# M623X.net
KiCad netlist of a schematic drawn in EAGLE
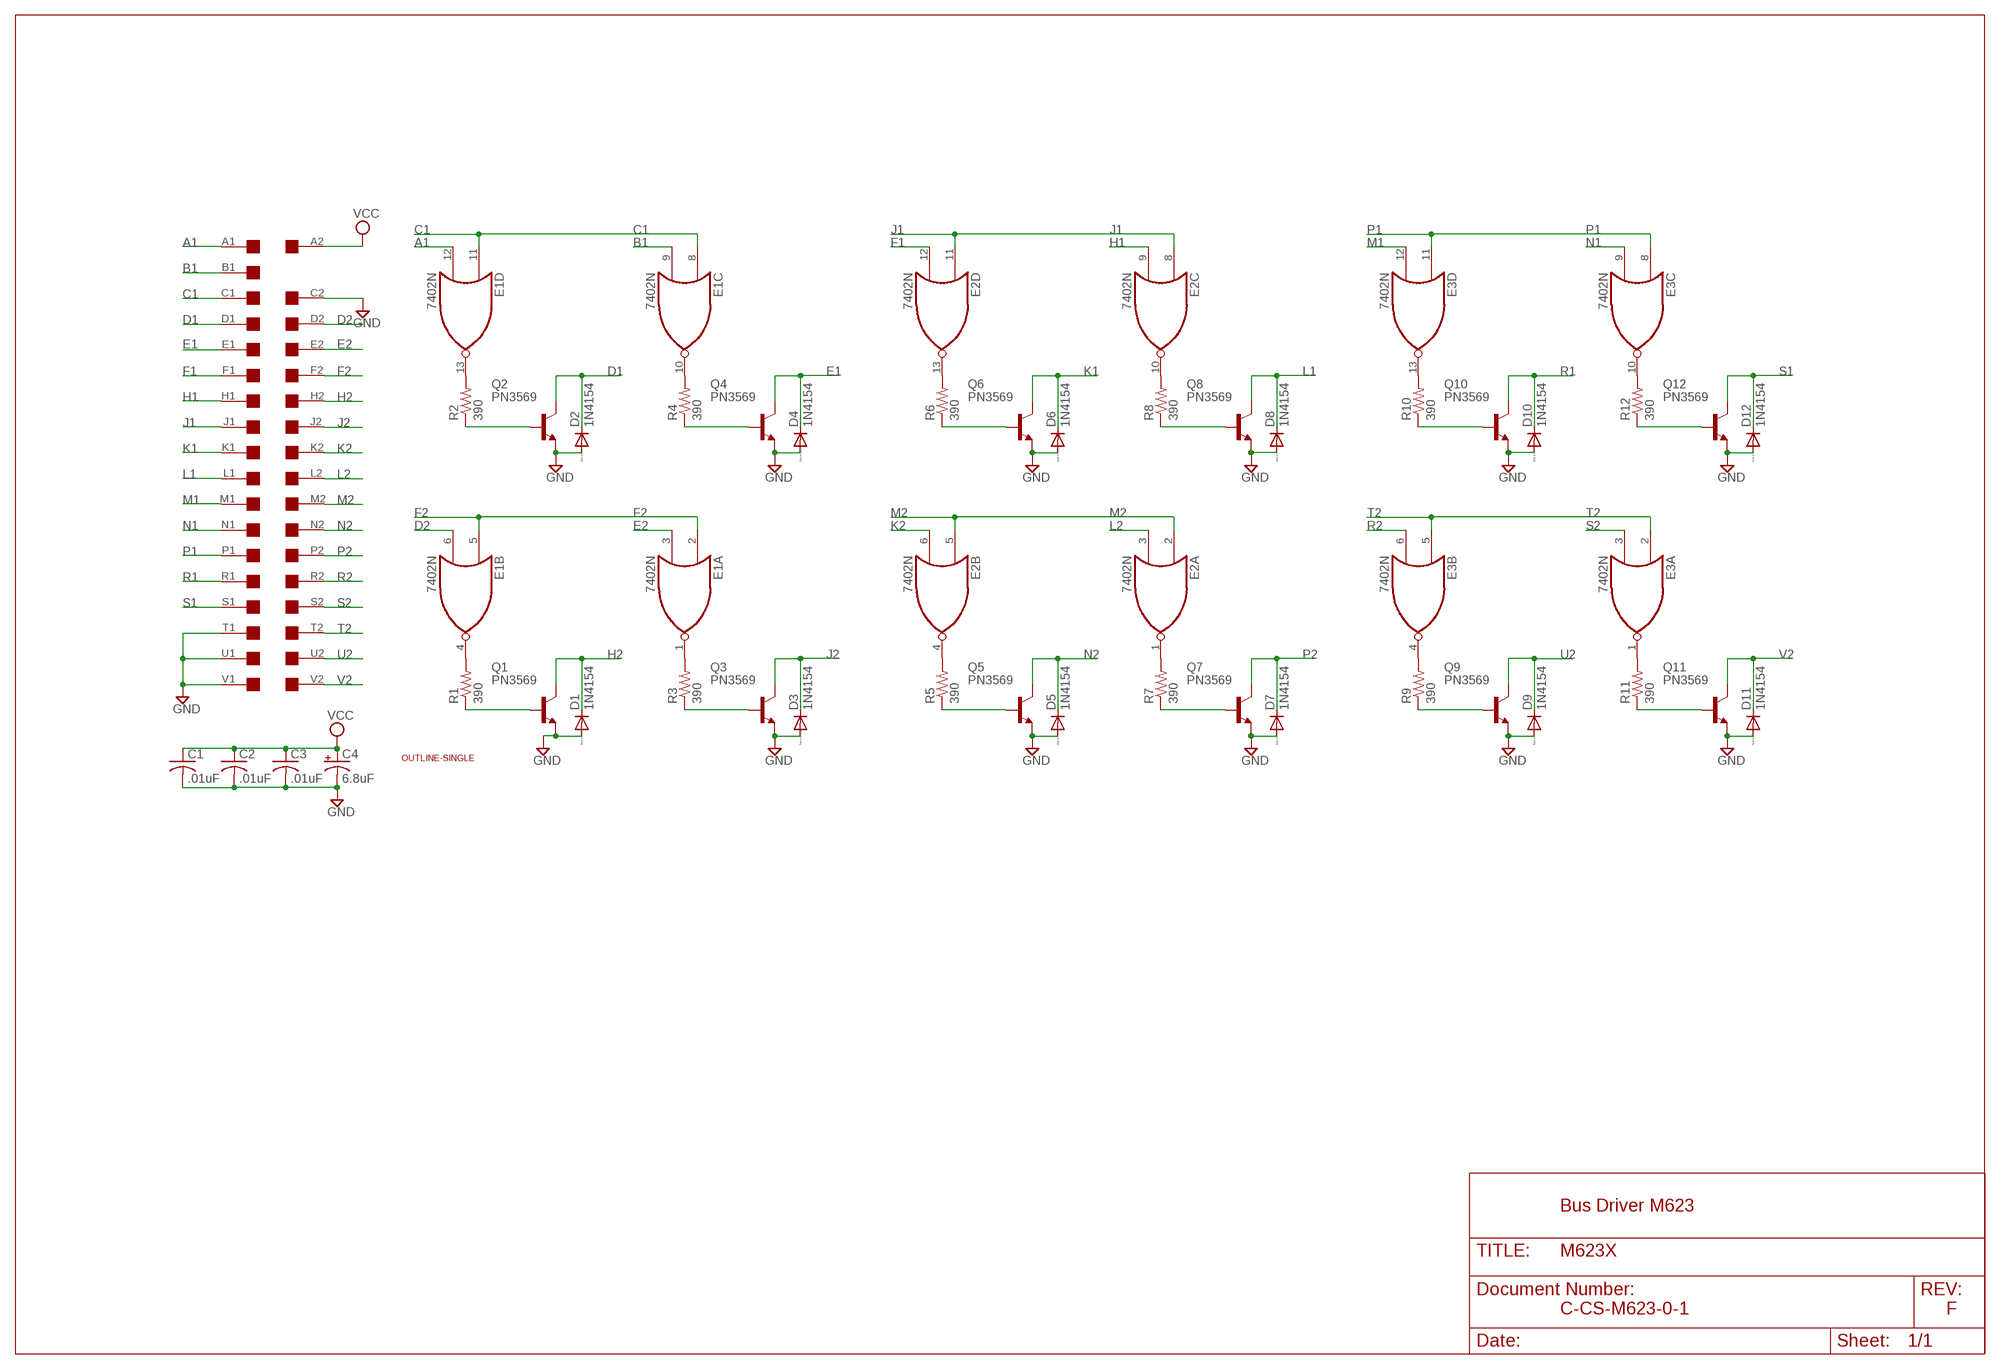
[diagram p0: schematic, sheet 1]

(export (version "E")
  (design (tool "Eeschema 10.0.6"))
  (components
    (comp (ref "C1")
      (value ".01uF")
      (footprint "eagle-import:C050-025X075")
      (libsource (lib "eagle-import") (part "C-US050-025X075"))
    )
    (comp (ref "C2")
      (value ".01uF")
      (footprint "eagle-import:C050-025X075")
      (libsource (lib "eagle-import") (part "C-US050-025X075"))
    )
    (comp (ref "C3")
      (value ".01uF")
      (footprint "eagle-import:C050-025X075")
      (libsource (lib "eagle-import") (part "C-US050-025X075"))
    )
    (comp (ref "C4")
      (value "6.8uF")
      (footprint "eagle-import:E12-8")
      (libsource (lib "eagle-import") (part "CPOL-USE20-8AXIAL"))
    )
    (comp (ref "D1")
      (value "1N4154")
      (footprint "eagle-import:DO35-10")
      (libsource (lib "eagle-import") (part "1N4148DO35-10"))
    )
    (comp (ref "D2")
      (value "1N4154")
      (footprint "eagle-import:DO35-10")
      (libsource (lib "eagle-import") (part "1N4148DO35-10"))
    )
    (comp (ref "D3")
      (value "1N4154")
      (footprint "eagle-import:DO35-10")
      (libsource (lib "eagle-import") (part "1N4148DO35-10"))
    )
    (comp (ref "D4")
      (value "1N4154")
      (footprint "eagle-import:DO35-10")
      (libsource (lib "eagle-import") (part "1N4148DO35-10"))
    )
    (comp (ref "D5")
      (value "1N4154")
      (footprint "eagle-import:DO35-10")
      (libsource (lib "eagle-import") (part "1N4148DO35-10"))
    )
    (comp (ref "D6")
      (value "1N4154")
      (footprint "eagle-import:DO35-10")
      (libsource (lib "eagle-import") (part "1N4148DO35-10"))
    )
    (comp (ref "D7")
      (value "1N4154")
      (footprint "eagle-import:DO35-10")
      (libsource (lib "eagle-import") (part "1N4148DO35-10"))
    )
    (comp (ref "D8")
      (value "1N4154")
      (footprint "eagle-import:DO35-10")
      (libsource (lib "eagle-import") (part "1N4148DO35-10"))
    )
    (comp (ref "D9")
      (value "1N4154")
      (footprint "eagle-import:DO35-10")
      (libsource (lib "eagle-import") (part "1N4148DO35-10"))
    )
    (comp (ref "D10")
      (value "1N4154")
      (footprint "eagle-import:DO35-10")
      (libsource (lib "eagle-import") (part "1N4148DO35-10"))
    )
    (comp (ref "D11")
      (value "1N4154")
      (footprint "eagle-import:DO35-10")
      (libsource (lib "eagle-import") (part "1N4148DO35-10"))
    )
    (comp (ref "D12")
      (value "1N4154")
      (footprint "eagle-import:DO35-10")
      (libsource (lib "eagle-import") (part "1N4148DO35-10"))
    )
    (comp (ref "E1")
      (value "7402N")
      (footprint "eagle-import:DIL14")
      (libsource (lib "eagle-import") (part "7402N"))
    )
    (comp (ref "E2")
      (value "7402N")
      (footprint "eagle-import:DIL14")
      (libsource (lib "eagle-import") (part "7402N"))
    )
    (comp (ref "E3")
      (value "7402N")
      (footprint "eagle-import:DIL14")
      (libsource (lib "eagle-import") (part "7402N"))
    )
    (comp (ref "Q1")
      (value "PN3569")
      (footprint "eagle-import:TO39")
      (libsource (lib "eagle-import") (part "-NPN-TO39-EBC2N1613"))
    )
    (comp (ref "Q2")
      (value "PN3569")
      (footprint "eagle-import:TO39")
      (libsource (lib "eagle-import") (part "-NPN-TO39-EBC2N1613"))
    )
    (comp (ref "Q3")
      (value "PN3569")
      (footprint "eagle-import:TO39")
      (libsource (lib "eagle-import") (part "-NPN-TO39-EBC2N1613"))
    )
    (comp (ref "Q4")
      (value "PN3569")
      (footprint "eagle-import:TO39")
      (libsource (lib "eagle-import") (part "-NPN-TO39-EBC2N1613"))
    )
    (comp (ref "Q5")
      (value "PN3569")
      (footprint "eagle-import:TO39")
      (libsource (lib "eagle-import") (part "-NPN-TO39-EBC2N1613"))
    )
    (comp (ref "Q6")
      (value "PN3569")
      (footprint "eagle-import:TO39")
      (libsource (lib "eagle-import") (part "-NPN-TO39-EBC2N1613"))
    )
    (comp (ref "Q7")
      (value "PN3569")
      (footprint "eagle-import:TO39")
      (libsource (lib "eagle-import") (part "-NPN-TO39-EBC2N1613"))
    )
    (comp (ref "Q8")
      (value "PN3569")
      (footprint "eagle-import:TO39")
      (libsource (lib "eagle-import") (part "-NPN-TO39-EBC2N1613"))
    )
    (comp (ref "Q9")
      (value "PN3569")
      (footprint "eagle-import:TO39")
      (libsource (lib "eagle-import") (part "-NPN-TO39-EBC2N1613"))
    )
    (comp (ref "Q10")
      (value "PN3569")
      (footprint "eagle-import:TO39")
      (libsource (lib "eagle-import") (part "-NPN-TO39-EBC2N1613"))
    )
    (comp (ref "Q11")
      (value "PN3569")
      (footprint "eagle-import:TO39")
      (libsource (lib "eagle-import") (part "-NPN-TO39-EBC2N1613"))
    )
    (comp (ref "Q12")
      (value "PN3569")
      (footprint "eagle-import:TO39")
      (libsource (lib "eagle-import") (part "-NPN-TO39-EBC2N1613"))
    )
    (comp (ref "R1")
      (value "390")
      (footprint "eagle-import:0207_10")
      (libsource (lib "eagle-import") (part "R-US_0207/10"))
    )
    (comp (ref "R2")
      (value "390")
      (footprint "eagle-import:0207_10")
      (libsource (lib "eagle-import") (part "R-US_0207/10"))
    )
    (comp (ref "R3")
      (value "390")
      (footprint "eagle-import:0207_10")
      (libsource (lib "eagle-import") (part "R-US_0207/10"))
    )
    (comp (ref "R4")
      (value "390")
      (footprint "eagle-import:0207_10")
      (libsource (lib "eagle-import") (part "R-US_0207/10"))
    )
    (comp (ref "R5")
      (value "390")
      (footprint "eagle-import:0207_10")
      (libsource (lib "eagle-import") (part "R-US_0207/10"))
    )
    (comp (ref "R6")
      (value "390")
      (footprint "eagle-import:0207_10")
      (libsource (lib "eagle-import") (part "R-US_0207/10"))
    )
    (comp (ref "R7")
      (value "390")
      (footprint "eagle-import:0207_10")
      (libsource (lib "eagle-import") (part "R-US_0207/10"))
    )
    (comp (ref "R8")
      (value "390")
      (footprint "eagle-import:0207_10")
      (libsource (lib "eagle-import") (part "R-US_0207/10"))
    )
    (comp (ref "R9")
      (value "390")
      (footprint "eagle-import:0207_10")
      (libsource (lib "eagle-import") (part "R-US_0207/10"))
    )
    (comp (ref "R10")
      (value "390")
      (footprint "eagle-import:0207_10")
      (libsource (lib "eagle-import") (part "R-US_0207/10"))
    )
    (comp (ref "R11")
      (value "390")
      (footprint "eagle-import:0207_10")
      (libsource (lib "eagle-import") (part "R-US_0207/10"))
    )
    (comp (ref "R12")
      (value "390")
      (footprint "eagle-import:0207_10")
      (libsource (lib "eagle-import") (part "R-US_0207/10"))
    )
    (comp (ref "U$1")
      (value "OUTLINE-SINGLE")
      (footprint "eagle-import:SINGLE")
      (libsource (lib "eagle-import") (part "OUTLINE-SINGLE"))
    )
    (comp (ref "U$4")
      (value "SINGLE")
      (footprint "eagle-import:EDGE-CON2")
      (libsource (lib "eagle-import") (part "SINGLE"))
    )
  )
  (nets
    (net (code "1") (name "/A1") (class "Default")
      (node (ref "E1") (pin "12") (pinfunction "I1_12") (pintype "input"))
      (node (ref "U$4") (pin "A1") (pinfunction "1_A1") (pintype "bidirectional"))
    )
    (net (code "2") (name "/B1") (class "Default")
      (node (ref "E1") (pin "9") (pinfunction "I1_9") (pintype "input"))
      (node (ref "U$4") (pin "B1") (pinfunction "1_B1") (pintype "bidirectional"))
    )
    (net (code "3") (name "/C1") (class "Default")
      (node (ref "E1") (pin "11") (pinfunction "I0_11") (pintype "input"))
      (node (ref "E1") (pin "8") (pinfunction "I0_8") (pintype "input"))
      (node (ref "U$4") (pin "C1") (pinfunction "1_C1") (pintype "bidirectional"))
    )
    (net (code "4") (name "/D1") (class "Default")
      (node (ref "D2") (pin "C") (pinfunction "C_C") (pintype "passive"))
      (node (ref "Q2") (pin "3") (pinfunction "C_3") (pintype "passive"))
      (node (ref "U$4") (pin "D1") (pinfunction "1_D1") (pintype "bidirectional"))
    )
    (net (code "5") (name "/D2") (class "Default")
      (node (ref "E1") (pin "6") (pinfunction "I1_6") (pintype "input"))
      (node (ref "U$4") (pin "D2") (pinfunction "1_D2") (pintype "bidirectional"))
    )
    (net (code "6") (name "/E1") (class "Default")
      (node (ref "D4") (pin "C") (pinfunction "C_C") (pintype "passive"))
      (node (ref "Q4") (pin "3") (pinfunction "C_3") (pintype "passive"))
      (node (ref "U$4") (pin "E1") (pinfunction "1_E1") (pintype "bidirectional"))
    )
    (net (code "7") (name "/E2") (class "Default")
      (node (ref "E1") (pin "3") (pinfunction "I1_3") (pintype "input"))
      (node (ref "U$4") (pin "E2") (pinfunction "1_E2") (pintype "bidirectional"))
    )
    (net (code "8") (name "/F1") (class "Default")
      (node (ref "E2") (pin "12") (pinfunction "I1_12") (pintype "input"))
      (node (ref "U$4") (pin "F1") (pinfunction "1_F1") (pintype "bidirectional"))
    )
    (net (code "9") (name "/F2") (class "Default")
      (node (ref "E1") (pin "2") (pinfunction "I0_2") (pintype "input"))
      (node (ref "E1") (pin "5") (pinfunction "I0_5") (pintype "input"))
      (node (ref "U$4") (pin "F2") (pinfunction "1_F2") (pintype "bidirectional"))
    )
    (net (code "10") (name "/H1") (class "Default")
      (node (ref "E2") (pin "9") (pinfunction "I1_9") (pintype "input"))
      (node (ref "U$4") (pin "H1") (pinfunction "1_H1") (pintype "bidirectional"))
    )
    (net (code "11") (name "/H2") (class "Default")
      (node (ref "D1") (pin "C") (pinfunction "C_C") (pintype "passive"))
      (node (ref "Q1") (pin "3") (pinfunction "C_3") (pintype "passive"))
      (node (ref "U$4") (pin "H2") (pinfunction "1_H2") (pintype "bidirectional"))
    )
    (net (code "12") (name "/J1") (class "Default")
      (node (ref "E2") (pin "11") (pinfunction "I0_11") (pintype "input"))
      (node (ref "E2") (pin "8") (pinfunction "I0_8") (pintype "input"))
      (node (ref "U$4") (pin "J1") (pinfunction "1_J1") (pintype "bidirectional"))
    )
    (net (code "13") (name "/J2") (class "Default")
      (node (ref "D3") (pin "C") (pinfunction "C_C") (pintype "passive"))
      (node (ref "Q3") (pin "3") (pinfunction "C_3") (pintype "passive"))
      (node (ref "U$4") (pin "J2") (pinfunction "1_J2") (pintype "bidirectional"))
    )
    (net (code "14") (name "/K1") (class "Default")
      (node (ref "D6") (pin "C") (pinfunction "C_C") (pintype "passive"))
      (node (ref "Q6") (pin "3") (pinfunction "C_3") (pintype "passive"))
      (node (ref "U$4") (pin "K1") (pinfunction "1_K1") (pintype "bidirectional"))
    )
    (net (code "15") (name "/K2") (class "Default")
      (node (ref "E2") (pin "6") (pinfunction "I1_6") (pintype "input"))
      (node (ref "U$4") (pin "K2") (pinfunction "1_K2") (pintype "bidirectional"))
    )
    (net (code "16") (name "/L1") (class "Default")
      (node (ref "D8") (pin "C") (pinfunction "C_C") (pintype "passive"))
      (node (ref "Q8") (pin "3") (pinfunction "C_3") (pintype "passive"))
      (node (ref "U$4") (pin "L1") (pinfunction "1_L1") (pintype "bidirectional"))
    )
    (net (code "17") (name "/L2") (class "Default")
      (node (ref "E2") (pin "3") (pinfunction "I1_3") (pintype "input"))
      (node (ref "U$4") (pin "L2") (pinfunction "1_L2") (pintype "bidirectional"))
    )
    (net (code "18") (name "/M1") (class "Default")
      (node (ref "E3") (pin "12") (pinfunction "I1_12") (pintype "input"))
      (node (ref "U$4") (pin "M1") (pinfunction "1_M1") (pintype "bidirectional"))
    )
    (net (code "19") (name "/M2") (class "Default")
      (node (ref "E2") (pin "2") (pinfunction "I0_2") (pintype "input"))
      (node (ref "E2") (pin "5") (pinfunction "I0_5") (pintype "input"))
      (node (ref "U$4") (pin "M2") (pinfunction "1_M2") (pintype "bidirectional"))
    )
    (net (code "20") (name "/N1") (class "Default")
      (node (ref "E3") (pin "9") (pinfunction "I1_9") (pintype "input"))
      (node (ref "U$4") (pin "N1") (pinfunction "1_N1") (pintype "bidirectional"))
    )
    (net (code "21") (name "/N2") (class "Default")
      (node (ref "D5") (pin "C") (pinfunction "C_C") (pintype "passive"))
      (node (ref "Q5") (pin "3") (pinfunction "C_3") (pintype "passive"))
      (node (ref "U$4") (pin "N2") (pinfunction "1_N2") (pintype "bidirectional"))
    )
    (net (code "22") (name "/P1") (class "Default")
      (node (ref "E3") (pin "11") (pinfunction "I0_11") (pintype "input"))
      (node (ref "E3") (pin "8") (pinfunction "I0_8") (pintype "input"))
      (node (ref "U$4") (pin "P1") (pinfunction "1_P1") (pintype "bidirectional"))
    )
    (net (code "23") (name "/P2") (class "Default")
      (node (ref "D7") (pin "C") (pinfunction "C_C") (pintype "passive"))
      (node (ref "Q7") (pin "3") (pinfunction "C_3") (pintype "passive"))
      (node (ref "U$4") (pin "P2") (pinfunction "1_P2") (pintype "bidirectional"))
    )
    (net (code "24") (name "/R1") (class "Default")
      (node (ref "D10") (pin "C") (pinfunction "C_C") (pintype "passive"))
      (node (ref "Q10") (pin "3") (pinfunction "C_3") (pintype "passive"))
      (node (ref "U$4") (pin "R1") (pinfunction "1_R1") (pintype "bidirectional"))
    )
    (net (code "25") (name "/R2") (class "Default")
      (node (ref "E3") (pin "6") (pinfunction "I1_6") (pintype "input"))
      (node (ref "U$4") (pin "R2") (pinfunction "1_R2") (pintype "bidirectional"))
    )
    (net (code "26") (name "/S1") (class "Default")
      (node (ref "D12") (pin "C") (pinfunction "C_C") (pintype "passive"))
      (node (ref "Q12") (pin "3") (pinfunction "C_3") (pintype "passive"))
      (node (ref "U$4") (pin "S1") (pinfunction "1_S1") (pintype "bidirectional"))
    )
    (net (code "27") (name "/S2") (class "Default")
      (node (ref "E3") (pin "3") (pinfunction "I1_3") (pintype "input"))
      (node (ref "U$4") (pin "S2") (pinfunction "1_S2") (pintype "bidirectional"))
    )
    (net (code "28") (name "/T2") (class "Default")
      (node (ref "E3") (pin "2") (pinfunction "I0_2") (pintype "input"))
      (node (ref "E3") (pin "5") (pinfunction "I0_5") (pintype "input"))
      (node (ref "U$4") (pin "T2") (pinfunction "1_T2") (pintype "bidirectional"))
    )
    (net (code "29") (name "/U2") (class "Default")
      (node (ref "D9") (pin "C") (pinfunction "C_C") (pintype "passive"))
      (node (ref "Q9") (pin "3") (pinfunction "C_3") (pintype "passive"))
      (node (ref "U$4") (pin "U2") (pinfunction "1_U2") (pintype "bidirectional"))
    )
    (net (code "30") (name "/V2") (class "Default")
      (node (ref "D11") (pin "C") (pinfunction "C_C") (pintype "passive"))
      (node (ref "Q11") (pin "3") (pinfunction "C_3") (pintype "passive"))
      (node (ref "U$4") (pin "V2") (pinfunction "1_V2") (pintype "bidirectional"))
    )
    (net (code "31") (name "GND") (class "Default")
      (node (ref "C1") (pin "2") (pinfunction "2_2") (pintype "passive"))
      (node (ref "C2") (pin "2") (pinfunction "2_2") (pintype "passive"))
      (node (ref "C3") (pin "2") (pinfunction "2_2") (pintype "passive"))
      (node (ref "C4") (pin "-") (pinfunction "-_-") (pintype "passive"))
      (node (ref "D1") (pin "A") (pinfunction "A_A") (pintype "passive"))
      (node (ref "D10") (pin "A") (pinfunction "A_A") (pintype "passive"))
      (node (ref "D11") (pin "A") (pinfunction "A_A") (pintype "passive"))
      (node (ref "D12") (pin "A") (pinfunction "A_A") (pintype "passive"))
      (node (ref "D2") (pin "A") (pinfunction "A_A") (pintype "passive"))
      (node (ref "D3") (pin "A") (pinfunction "A_A") (pintype "passive"))
      (node (ref "D4") (pin "A") (pinfunction "A_A") (pintype "passive"))
      (node (ref "D5") (pin "A") (pinfunction "A_A") (pintype "passive"))
      (node (ref "D6") (pin "A") (pinfunction "A_A") (pintype "passive"))
      (node (ref "D7") (pin "A") (pinfunction "A_A") (pintype "passive"))
      (node (ref "D8") (pin "A") (pinfunction "A_A") (pintype "passive"))
      (node (ref "D9") (pin "A") (pinfunction "A_A") (pintype "passive"))
      (node (ref "Q1") (pin "1") (pinfunction "E_1") (pintype "passive"))
      (node (ref "Q10") (pin "1") (pinfunction "E_1") (pintype "passive"))
      (node (ref "Q11") (pin "1") (pinfunction "E_1") (pintype "passive"))
      (node (ref "Q12") (pin "1") (pinfunction "E_1") (pintype "passive"))
      (node (ref "Q2") (pin "1") (pinfunction "E_1") (pintype "passive"))
      (node (ref "Q3") (pin "1") (pinfunction "E_1") (pintype "passive"))
      (node (ref "Q4") (pin "1") (pinfunction "E_1") (pintype "passive"))
      (node (ref "Q5") (pin "1") (pinfunction "E_1") (pintype "passive"))
      (node (ref "Q6") (pin "1") (pinfunction "E_1") (pintype "passive"))
      (node (ref "Q7") (pin "1") (pinfunction "E_1") (pintype "passive"))
      (node (ref "Q8") (pin "1") (pinfunction "E_1") (pintype "passive"))
      (node (ref "Q9") (pin "1") (pinfunction "E_1") (pintype "passive"))
      (node (ref "U$4") (pin "C2") (pinfunction "1_C2") (pintype "bidirectional"))
      (node (ref "U$4") (pin "T1") (pinfunction "1_T1") (pintype "bidirectional"))
      (node (ref "U$4") (pin "U1") (pinfunction "1_U1") (pintype "bidirectional"))
      (node (ref "U$4") (pin "V1") (pinfunction "1_V1") (pintype "bidirectional"))
    )
    (net (code "32") (name "Net-(E1A-O)") (class "Default")
      (node (ref "E1") (pin "1") (pinfunction "O_1") (pintype "output"))
      (node (ref "R3") (pin "2") (pinfunction "2_2") (pintype "passive"))
    )
    (net (code "33") (name "Net-(E1B-O)") (class "Default")
      (node (ref "E1") (pin "4") (pinfunction "O_4") (pintype "output"))
      (node (ref "R1") (pin "2") (pinfunction "2_2") (pintype "passive"))
    )
    (net (code "34") (name "Net-(E1C-O)") (class "Default")
      (node (ref "E1") (pin "10") (pinfunction "O_10") (pintype "output"))
      (node (ref "R4") (pin "2") (pinfunction "2_2") (pintype "passive"))
    )
    (net (code "35") (name "Net-(E1D-O)") (class "Default")
      (node (ref "E1") (pin "13") (pinfunction "O_13") (pintype "output"))
      (node (ref "R2") (pin "2") (pinfunction "2_2") (pintype "passive"))
    )
    (net (code "36") (name "Net-(E2A-O)") (class "Default")
      (node (ref "E2") (pin "1") (pinfunction "O_1") (pintype "output"))
      (node (ref "R7") (pin "2") (pinfunction "2_2") (pintype "passive"))
    )
    (net (code "37") (name "Net-(E2B-O)") (class "Default")
      (node (ref "E2") (pin "4") (pinfunction "O_4") (pintype "output"))
      (node (ref "R5") (pin "2") (pinfunction "2_2") (pintype "passive"))
    )
    (net (code "38") (name "Net-(E2C-O)") (class "Default")
      (node (ref "E2") (pin "10") (pinfunction "O_10") (pintype "output"))
      (node (ref "R8") (pin "2") (pinfunction "2_2") (pintype "passive"))
    )
    (net (code "39") (name "Net-(E2D-O)") (class "Default")
      (node (ref "E2") (pin "13") (pinfunction "O_13") (pintype "output"))
      (node (ref "R6") (pin "2") (pinfunction "2_2") (pintype "passive"))
    )
    (net (code "40") (name "Net-(E3A-O)") (class "Default")
      (node (ref "E3") (pin "1") (pinfunction "O_1") (pintype "output"))
      (node (ref "R11") (pin "2") (pinfunction "2_2") (pintype "passive"))
    )
    (net (code "41") (name "Net-(E3B-O)") (class "Default")
      (node (ref "E3") (pin "4") (pinfunction "O_4") (pintype "output"))
      (node (ref "R9") (pin "2") (pinfunction "2_2") (pintype "passive"))
    )
    (net (code "42") (name "Net-(E3C-O)") (class "Default")
      (node (ref "E3") (pin "10") (pinfunction "O_10") (pintype "output"))
      (node (ref "R12") (pin "2") (pinfunction "2_2") (pintype "passive"))
    )
    (net (code "43") (name "Net-(E3D-O)") (class "Default")
      (node (ref "E3") (pin "13") (pinfunction "O_13") (pintype "output"))
      (node (ref "R10") (pin "2") (pinfunction "2_2") (pintype "passive"))
    )
    (net (code "44") (name "Net-(Q1-B)") (class "Default")
      (node (ref "Q1") (pin "2") (pinfunction "B_2") (pintype "passive"))
      (node (ref "R1") (pin "1") (pinfunction "1_1") (pintype "passive"))
    )
    (net (code "45") (name "Net-(Q2-B)") (class "Default")
      (node (ref "Q2") (pin "2") (pinfunction "B_2") (pintype "passive"))
      (node (ref "R2") (pin "1") (pinfunction "1_1") (pintype "passive"))
    )
    (net (code "46") (name "Net-(Q3-B)") (class "Default")
      (node (ref "Q3") (pin "2") (pinfunction "B_2") (pintype "passive"))
      (node (ref "R3") (pin "1") (pinfunction "1_1") (pintype "passive"))
    )
    (net (code "47") (name "Net-(Q4-B)") (class "Default")
      (node (ref "Q4") (pin "2") (pinfunction "B_2") (pintype "passive"))
      (node (ref "R4") (pin "1") (pinfunction "1_1") (pintype "passive"))
    )
    (net (code "48") (name "Net-(Q5-B)") (class "Default")
      (node (ref "Q5") (pin "2") (pinfunction "B_2") (pintype "passive"))
      (node (ref "R5") (pin "1") (pinfunction "1_1") (pintype "passive"))
    )
    (net (code "49") (name "Net-(Q6-B)") (class "Default")
      (node (ref "Q6") (pin "2") (pinfunction "B_2") (pintype "passive"))
      (node (ref "R6") (pin "1") (pinfunction "1_1") (pintype "passive"))
    )
    (net (code "50") (name "Net-(Q7-B)") (class "Default")
      (node (ref "Q7") (pin "2") (pinfunction "B_2") (pintype "passive"))
      (node (ref "R7") (pin "1") (pinfunction "1_1") (pintype "passive"))
    )
    (net (code "51") (name "Net-(Q8-B)") (class "Default")
      (node (ref "Q8") (pin "2") (pinfunction "B_2") (pintype "passive"))
      (node (ref "R8") (pin "1") (pinfunction "1_1") (pintype "passive"))
    )
    (net (code "52") (name "Net-(Q9-B)") (class "Default")
      (node (ref "Q9") (pin "2") (pinfunction "B_2") (pintype "passive"))
      (node (ref "R9") (pin "1") (pinfunction "1_1") (pintype "passive"))
    )
    (net (code "53") (name "Net-(Q10-B)") (class "Default")
      (node (ref "Q10") (pin "2") (pinfunction "B_2") (pintype "passive"))
      (node (ref "R10") (pin "1") (pinfunction "1_1") (pintype "passive"))
    )
    (net (code "54") (name "Net-(Q11-B)") (class "Default")
      (node (ref "Q11") (pin "2") (pinfunction "B_2") (pintype "passive"))
      (node (ref "R11") (pin "1") (pinfunction "1_1") (pintype "passive"))
    )
    (net (code "55") (name "Net-(Q12-B)") (class "Default")
      (node (ref "Q12") (pin "2") (pinfunction "B_2") (pintype "passive"))
      (node (ref "R12") (pin "1") (pinfunction "1_1") (pintype "passive"))
    )
    (net (code "56") (name "VCC") (class "Default")
      (node (ref "C1") (pin "1") (pinfunction "1_1") (pintype "passive"))
      (node (ref "C2") (pin "1") (pinfunction "1_1") (pintype "passive"))
      (node (ref "C3") (pin "1") (pinfunction "1_1") (pintype "passive"))
      (node (ref "C4") (pin "+") (pinfunction "+_+") (pintype "passive"))
      (node (ref "U$4") (pin "A2") (pinfunction "1_A2") (pintype "bidirectional"))
    )
  )
)
